# MPHS.net
KiCad netlist of a schematic drawn in EAGLE
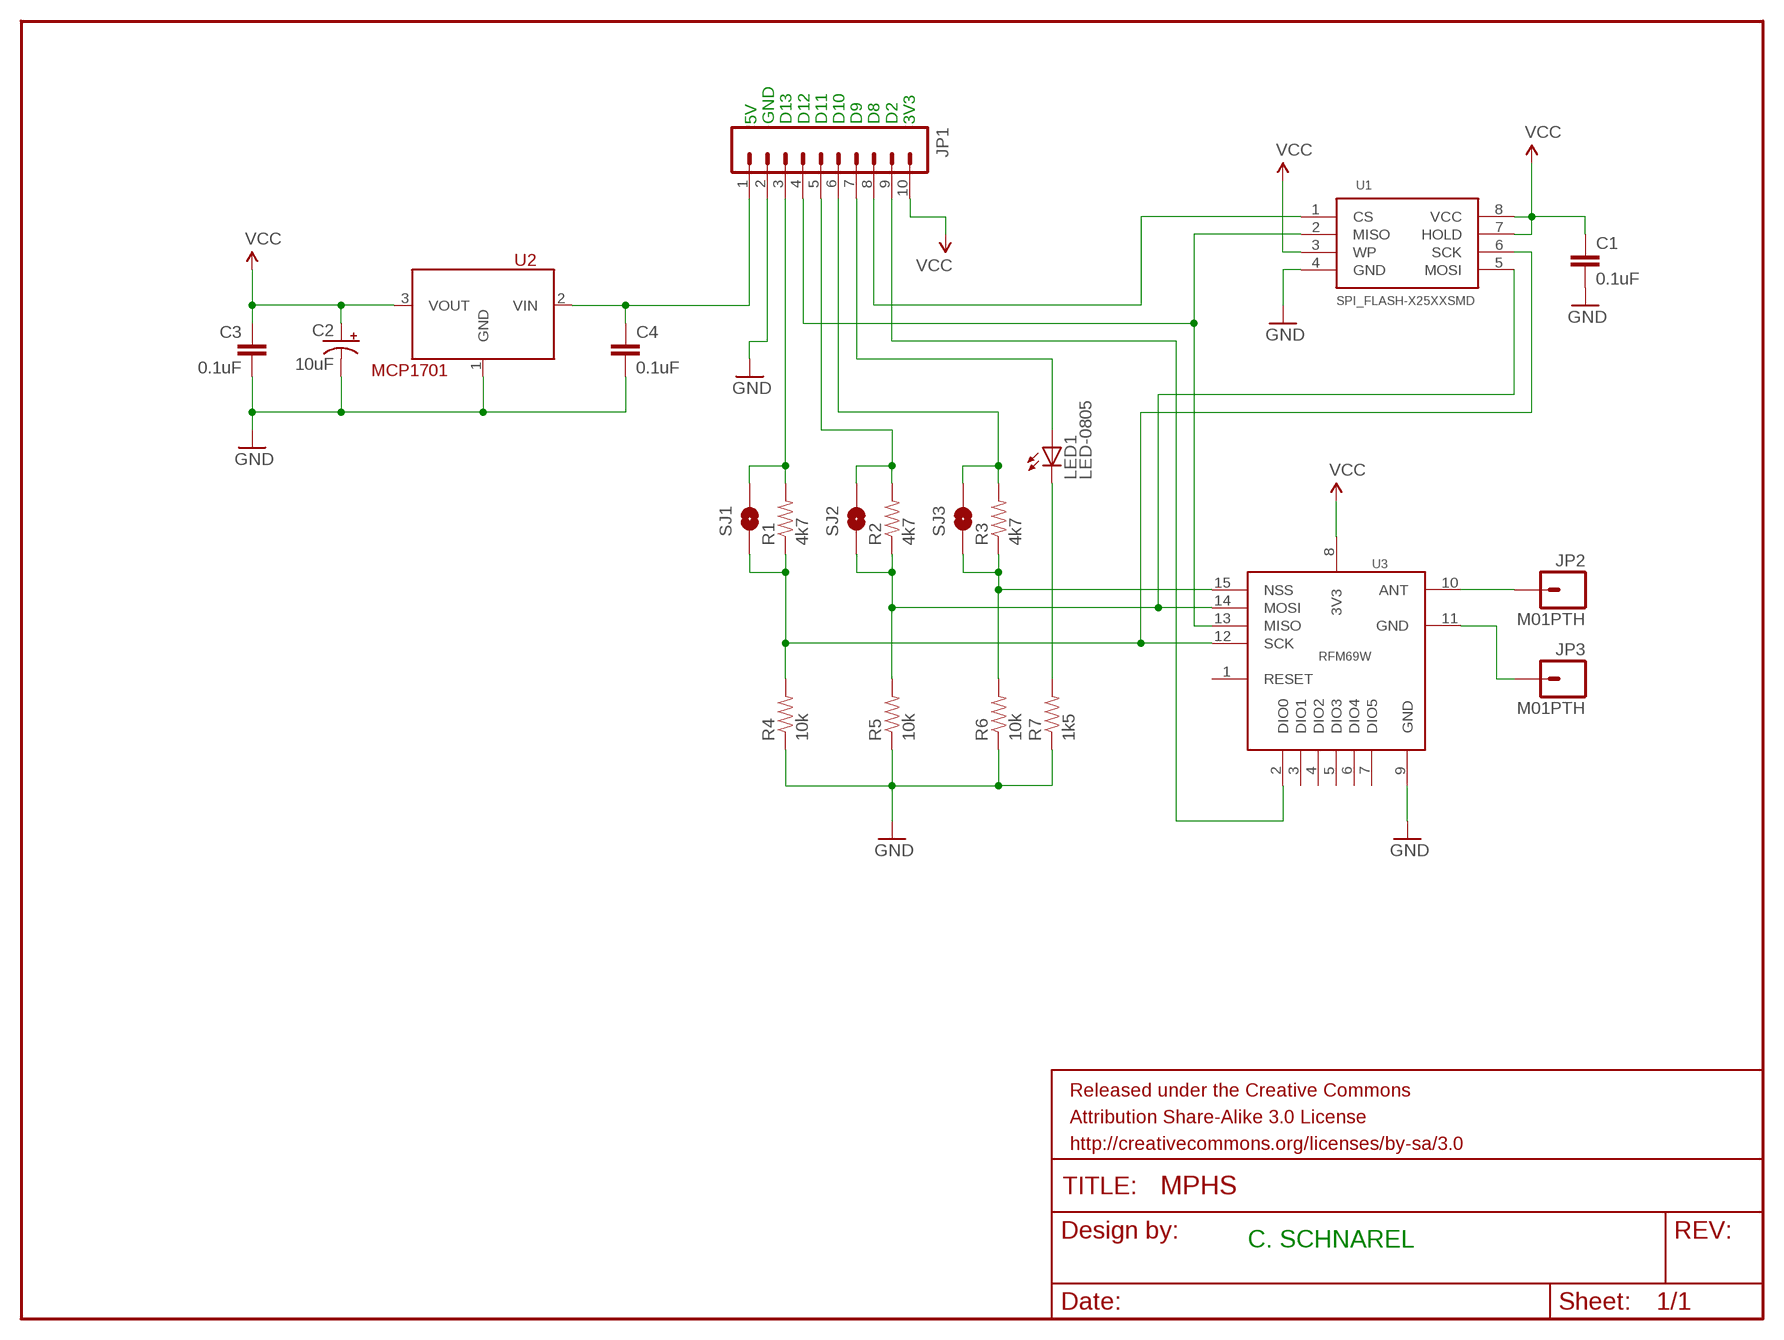
[diagram p0: schematic, sheet 1]

(export (version "E")
  (design (tool "Eeschema 10.0.6"))
  (components
    (comp (ref "C1")
      (value "0.1uF")
      (footprint "eagle-import:0805")
      (libsource (lib "eagle-import") (part "CAP0805"))
    )
    (comp (ref "C2")
      (value "10uF")
      (footprint "eagle-import:0805-POL")
      (libsource (lib "eagle-import") (part "CAP_POL0805"))
    )
    (comp (ref "C3")
      (value "0.1uF")
      (footprint "eagle-import:0805")
      (libsource (lib "eagle-import") (part "CAP0805"))
    )
    (comp (ref "C4")
      (value "0.1uF")
      (footprint "eagle-import:0805")
      (libsource (lib "eagle-import") (part "CAP0805"))
    )
    (comp (ref "FRAME1")
      (value "FRAME-LETTER")
      (footprint "eagle-import:CREATIVE_COMMONS")
      (libsource (lib "eagle-import") (part "FRAME-LETTER"))
    )
    (comp (ref "JP1")
      (value "M10\"")
      (footprint "eagle-import:1X10")
      (libsource (lib "eagle-import") (part "M10{dblquote}"))
    )
    (comp (ref "JP2")
      (value "M01PTH")
      (footprint "eagle-import:1X01")
      (libsource (lib "eagle-import") (part "M01PTH"))
    )
    (comp (ref "JP3")
      (value "M01PTH")
      (footprint "eagle-import:1X01")
      (libsource (lib "eagle-import") (part "M01PTH"))
    )
    (comp (ref "LED1")
      (value "LED-0805")
      (footprint "eagle-import:0805-LED")
      (libsource (lib "eagle-import") (part "LED-0805"))
    )
    (comp (ref "R1")
      (value "4k7")
      (footprint "eagle-import:0805")
      (libsource (lib "eagle-import") (part "RESISTOR0805-RES"))
    )
    (comp (ref "R2")
      (value "4k7")
      (footprint "eagle-import:0805")
      (libsource (lib "eagle-import") (part "RESISTOR0805-RES"))
    )
    (comp (ref "R3")
      (value "4k7")
      (footprint "eagle-import:0805")
      (libsource (lib "eagle-import") (part "RESISTOR0805-RES"))
    )
    (comp (ref "R4")
      (value "10k")
      (footprint "eagle-import:0805")
      (libsource (lib "eagle-import") (part "RESISTOR0805-RES"))
    )
    (comp (ref "R5")
      (value "10k")
      (footprint "eagle-import:0805")
      (libsource (lib "eagle-import") (part "RESISTOR0805-RES"))
    )
    (comp (ref "R6")
      (value "10k")
      (footprint "eagle-import:0805")
      (libsource (lib "eagle-import") (part "RESISTOR0805-RES"))
    )
    (comp (ref "R7")
      (value "1k5")
      (footprint "eagle-import:0805")
      (libsource (lib "eagle-import") (part "RESISTOR0805-RES"))
    )
    (comp (ref "SJ1")
      (value "SOLDERJUMPERNO")
      (footprint "eagle-import:SJ_2S-NO")
      (libsource (lib "eagle-import") (part "SOLDERJUMPERNO"))
    )
    (comp (ref "SJ2")
      (value "SOLDERJUMPERNO")
      (footprint "eagle-import:SJ_2S-NO")
      (libsource (lib "eagle-import") (part "SOLDERJUMPERNO"))
    )
    (comp (ref "SJ3")
      (value "SOLDERJUMPERNO")
      (footprint "eagle-import:SJ_2S-NO")
      (libsource (lib "eagle-import") (part "SOLDERJUMPERNO"))
    )
    (comp (ref "U1")
      (value "SPI_FLASH-X25XXSMD")
      (footprint "eagle-import:SO08")
      (libsource (lib "eagle-import") (part "SPI_FLASH-X25XXSMD"))
    )
    (comp (ref "U2")
      (value "MCP1701")
      (footprint "eagle-import:SOT-89")
      (libsource (lib "eagle-import") (part "MCP1701"))
    )
    (comp (ref "U3")
      (value "RFM69W")
      (footprint "eagle-import:RFM69W")
      (libsource (lib "eagle-import") (part "RFM69W"))
    )
  )
  (nets
    (net (code "1") (name "GND") (class "Default")
      (node (ref "C1") (pin "2") (pinfunction "2_2") (pintype "passive"))
      (node (ref "C2") (pin "2") (pinfunction "-_2") (pintype "passive"))
      (node (ref "C3") (pin "2") (pinfunction "2_2") (pintype "passive"))
      (node (ref "C4") (pin "2") (pinfunction "2_2") (pintype "passive"))
      (node (ref "JP1") (pin "2") (pinfunction "2_2") (pintype "passive"))
      (node (ref "R4") (pin "1") (pinfunction "1_1") (pintype "passive"))
      (node (ref "R5") (pin "1") (pinfunction "1_1") (pintype "passive"))
      (node (ref "R6") (pin "1") (pinfunction "1_1") (pintype "passive"))
      (node (ref "R7") (pin "1") (pinfunction "1_1") (pintype "passive"))
      (node (ref "U1") (pin "4") (pinfunction "GND_4") (pintype "bidirectional"))
      (node (ref "U2") (pin "1") (pinfunction "GND_1") (pintype "bidirectional"))
      (node (ref "U3") (pin "9") (pinfunction "GND_9") (pintype "bidirectional"))
    )
    (net (code "2") (name "Net-(JP1-Pad3)") (class "Default")
      (node (ref "JP1") (pin "3") (pinfunction "3_3") (pintype "passive"))
      (node (ref "R1") (pin "2") (pinfunction "2_2") (pintype "passive"))
      (node (ref "SJ1") (pin "2") (pinfunction "2_2") (pintype "passive"))
    )
    (net (code "3") (name "Net-(JP1-Pad5)") (class "Default")
      (node (ref "JP1") (pin "5") (pinfunction "5_5") (pintype "passive"))
      (node (ref "R2") (pin "2") (pinfunction "2_2") (pintype "passive"))
      (node (ref "SJ2") (pin "2") (pinfunction "2_2") (pintype "passive"))
    )
    (net (code "4") (name "Net-(JP1-Pad6)") (class "Default")
      (node (ref "JP1") (pin "6") (pinfunction "6_6") (pintype "passive"))
      (node (ref "R3") (pin "2") (pinfunction "2_2") (pintype "passive"))
      (node (ref "SJ3") (pin "2") (pinfunction "2_2") (pintype "passive"))
    )
    (net (code "5") (name "Net-(JP1-Pad7)") (class "Default")
      (node (ref "JP1") (pin "7") (pinfunction "7_7") (pintype "passive"))
      (node (ref "LED1") (pin "A") (pinfunction "A_A") (pintype "passive"))
    )
    (net (code "6") (name "Net-(JP3-Pad1)") (class "Default")
      (node (ref "JP3") (pin "1") (pinfunction "1_1") (pintype "passive"))
      (node (ref "U3") (pin "11") (pinfunction "GND_11") (pintype "bidirectional"))
    )
    (net (code "7") (name "Net-(LED1-PadC)") (class "Default")
      (node (ref "LED1") (pin "C") (pinfunction "C_C") (pintype "passive"))
      (node (ref "R7") (pin "2") (pinfunction "2_2") (pintype "passive"))
    )
    (net (code "8") (name "Net-(U1-CS)") (class "Default")
      (node (ref "JP1") (pin "8") (pinfunction "8_8") (pintype "passive"))
      (node (ref "U1") (pin "1") (pinfunction "CS_1") (pintype "bidirectional"))
    )
    (net (code "9") (name "Net-(U1-MISO)") (class "Default")
      (node (ref "JP1") (pin "4") (pinfunction "4_4") (pintype "passive"))
      (node (ref "U1") (pin "2") (pinfunction "MISO_2") (pintype "bidirectional"))
      (node (ref "U3") (pin "13") (pinfunction "MISO_13") (pintype "bidirectional"))
    )
    (net (code "10") (name "Net-(U1-MOSI)") (class "Default")
      (node (ref "R2") (pin "1") (pinfunction "1_1") (pintype "passive"))
      (node (ref "R5") (pin "2") (pinfunction "2_2") (pintype "passive"))
      (node (ref "SJ2") (pin "1") (pinfunction "1_1") (pintype "passive"))
      (node (ref "U1") (pin "5") (pinfunction "MOSI_5") (pintype "bidirectional"))
      (node (ref "U3") (pin "14") (pinfunction "MOSI_14") (pintype "bidirectional"))
    )
    (net (code "11") (name "Net-(U1-SCK)") (class "Default")
      (node (ref "R1") (pin "1") (pinfunction "1_1") (pintype "passive"))
      (node (ref "R4") (pin "2") (pinfunction "2_2") (pintype "passive"))
      (node (ref "SJ1") (pin "1") (pinfunction "1_1") (pintype "passive"))
      (node (ref "U1") (pin "6") (pinfunction "SCK_6") (pintype "bidirectional"))
      (node (ref "U3") (pin "12") (pinfunction "SCK_12") (pintype "bidirectional"))
    )
    (net (code "12") (name "Net-(U2-VIN)") (class "Default")
      (node (ref "C4") (pin "1") (pinfunction "1_1") (pintype "passive"))
      (node (ref "JP1") (pin "1") (pinfunction "1_1") (pintype "passive"))
      (node (ref "U2") (pin "2") (pinfunction "VIN_2") (pintype "bidirectional"))
    )
    (net (code "13") (name "Net-(U3-ANT)") (class "Default")
      (node (ref "JP2") (pin "1") (pinfunction "1_1") (pintype "passive"))
      (node (ref "U3") (pin "10") (pinfunction "ANT_10") (pintype "bidirectional"))
    )
    (net (code "14") (name "Net-(U3-DIO0)") (class "Default")
      (node (ref "JP1") (pin "9") (pinfunction "9_9") (pintype "passive"))
      (node (ref "U3") (pin "2") (pinfunction "DIO0_2") (pintype "bidirectional"))
    )
    (net (code "15") (name "Net-(U3-NSS)") (class "Default")
      (node (ref "R3") (pin "1") (pinfunction "1_1") (pintype "passive"))
      (node (ref "R6") (pin "2") (pinfunction "2_2") (pintype "passive"))
      (node (ref "SJ3") (pin "1") (pinfunction "1_1") (pintype "passive"))
      (node (ref "U3") (pin "15") (pinfunction "NSS_15") (pintype "bidirectional"))
    )
    (net (code "16") (name "VCC") (class "Default")
      (node (ref "C1") (pin "1") (pinfunction "1_1") (pintype "passive"))
      (node (ref "C2") (pin "1") (pinfunction "+_1") (pintype "passive"))
      (node (ref "C3") (pin "1") (pinfunction "1_1") (pintype "passive"))
      (node (ref "JP1") (pin "10") (pinfunction "10_10") (pintype "passive"))
      (node (ref "U1") (pin "3") (pinfunction "WP_3") (pintype "bidirectional"))
      (node (ref "U1") (pin "7") (pinfunction "HOLD_7") (pintype "bidirectional"))
      (node (ref "U1") (pin "8") (pinfunction "VCC_8") (pintype "bidirectional"))
      (node (ref "U2") (pin "3") (pinfunction "VOUT_3") (pintype "bidirectional"))
      (node (ref "U3") (pin "8") (pinfunction "3V3_8") (pintype "bidirectional"))
    )
    (net (code "17") (name "unconnected-(U3-DIO1-Pad3)") (class "Default")
      (node (ref "U3") (pin "3") (pinfunction "DIO1_3") (pintype "bidirectional"))
    )
    (net (code "18") (name "unconnected-(U3-DIO2-Pad4)") (class "Default")
      (node (ref "U3") (pin "4") (pinfunction "DIO2_4") (pintype "bidirectional"))
    )
    (net (code "19") (name "unconnected-(U3-DIO3-Pad5)") (class "Default")
      (node (ref "U3") (pin "5") (pinfunction "DIO3_5") (pintype "bidirectional"))
    )
    (net (code "20") (name "unconnected-(U3-DIO4-Pad6)") (class "Default")
      (node (ref "U3") (pin "6") (pinfunction "DIO4_6") (pintype "bidirectional"))
    )
    (net (code "21") (name "unconnected-(U3-DIO5-Pad7)") (class "Default")
      (node (ref "U3") (pin "7") (pinfunction "DIO5_7") (pintype "bidirectional"))
    )
    (net (code "22") (name "unconnected-(U3-RESET-Pad1)") (class "Default")
      (node (ref "U3") (pin "1") (pinfunction "RESET_1") (pintype "bidirectional"))
    )
  )
)
